# Sheet1.net
KiCad netlist of a schematic drawn in Altium Designer
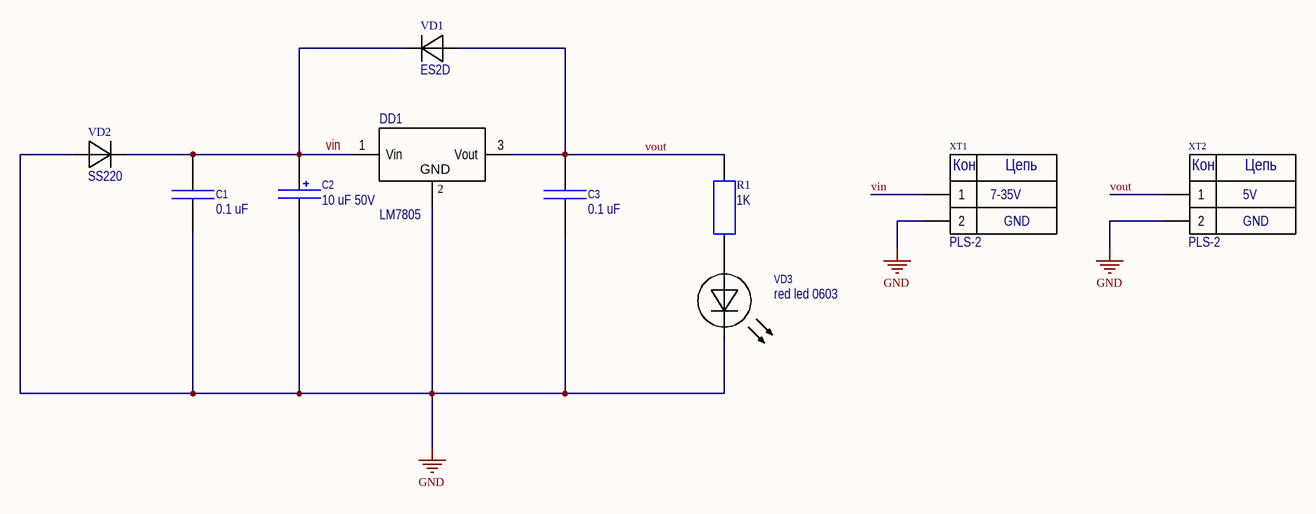
[diagram p0: Sheet1.SchDoc]

(export (version "E")
  (design (tool "Eeschema 10.0.6"))
  (components
    (comp (ref "C1")
      (value "0.1 uF")
      (footprint "Cap_0603")
      (description "Конденсатор")
      (fields (field (name "Comment") "Capacitor"))
      (libsource (lib "Alex_Lib") (part "Capacitor"))
    )
    (comp (ref "C2")
      (value "10 uF 50V")
      (footprint "CapDip5S")
      (description "Конденсатор эл-лит")
      (fields (field (name "Comment") "Capacitor_Polar"))
      (libsource (lib "Alex_Lib") (part "Capacitor_Polar"))
    )
    (comp (ref "C3")
      (value "0.1 uF")
      (footprint "Cap_0603")
      (description "Конденсатор")
      (fields (field (name "Comment") "Capacitor"))
      (libsource (lib "Alex_Lib") (part "Capacitor"))
    )
    (comp (ref "DD1")
      (value "Стабилизатор")
      (footprint "TO-220A-L")
      (fields (field (name "NAME") "LM7805"))
      (libsource (lib "Alex_Lib") (part "Стабилизатор"))
    )
    (comp (ref "R1")
      (value "1K")
      (footprint "RES_0603")
      (description "Резистор")
      (fields (field (name "Comment") "Resistor"))
      (libsource (lib "Alex_Lib") (part "Resistor"))
    )
    (comp (ref "VD1")
      (value "Diode")
      (footprint "SMB")
      (description "Диод")
      (fields (field (name "NAME") "ES2D"))
      (libsource (lib "Alex_Lib") (part "Diode"))
    )
    (comp (ref "VD2")
      (value "Diode")
      (footprint "SMB")
      (description "Диод")
      (fields (field (name "NAME") "SS220"))
      (libsource (lib "Alex_Lib") (part "Diode"))
    )
    (comp (ref "VD3")
      (value "red led 0603")
      (footprint "LED 0603_1608 RED")
      (description "Светодиод")
      (fields (field (name "Comment") "LED"))
      (libsource (lib "Alex_Lib") (part "LED"))
    )
    (comp (ref "XT1")
      (value "PLS-2")
      (footprint "PLS-2")
      (description "Header 1x3")
      (fields (field (name "Comment") "Header 1x2"))
      (libsource (lib "Alex_Lib") (part "Header 1x2"))
    )
    (comp (ref "XT2")
      (value "PLS-2")
      (footprint "PLS-2")
      (description "Header 1x3")
      (fields (field (name "Comment") "Header 1x2"))
      (libsource (lib "Alex_Lib") (part "Header 1x2"))
    )
  )
  (nets
    (net (code "1") (name "/vin") (class "Default")
      (node (ref "C1") (pin "2") (pinfunction "2_2") (pintype "passive"))
      (node (ref "C2") (pin "1") (pinfunction "1_1") (pintype "passive"))
      (node (ref "DD1") (pin "1") (pinfunction "Vin_1") (pintype "passive"))
      (node (ref "VD1") (pin "2") (pinfunction "2_2") (pintype "passive"))
      (node (ref "VD2") (pin "2") (pinfunction "2_2") (pintype "passive"))
      (node (ref "XT1") (pin "1") (pinfunction "1_1") (pintype "passive"))
    )
    (net (code "2") (name "/vout") (class "Default")
      (node (ref "C3") (pin "2") (pinfunction "2_2") (pintype "passive"))
      (node (ref "DD1") (pin "3") (pinfunction "Vout_3") (pintype "passive"))
      (node (ref "R1") (pin "2") (pinfunction "2_2") (pintype "passive"))
      (node (ref "VD1") (pin "1") (pinfunction "1_1") (pintype "passive"))
      (node (ref "XT2") (pin "1") (pinfunction "1_1") (pintype "passive"))
    )
    (net (code "3") (name "GND") (class "Default")
      (node (ref "C1") (pin "1") (pinfunction "1_1") (pintype "passive"))
      (node (ref "C2") (pin "2") (pinfunction "2_2") (pintype "passive"))
      (node (ref "C3") (pin "1") (pinfunction "1_1") (pintype "passive"))
      (node (ref "DD1") (pin "2") (pinfunction "GND_2") (pintype "passive"))
      (node (ref "VD2") (pin "1") (pinfunction "1_1") (pintype "passive"))
      (node (ref "VD3") (pin "2") (pinfunction "2_2") (pintype "passive"))
      (node (ref "XT1") (pin "2") (pinfunction "2_2") (pintype "passive"))
      (node (ref "XT2") (pin "2") (pinfunction "2_2") (pintype "passive"))
    )
    (net (code "4") (name "Net-(R1-Pad1)") (class "Default")
      (node (ref "R1") (pin "1") (pinfunction "1_1") (pintype "passive"))
      (node (ref "VD3") (pin "1") (pinfunction "1_1") (pintype "passive"))
    )
  )
)
